# Sensor_Board.net
KiCad netlist of a schematic drawn in Altium Designer
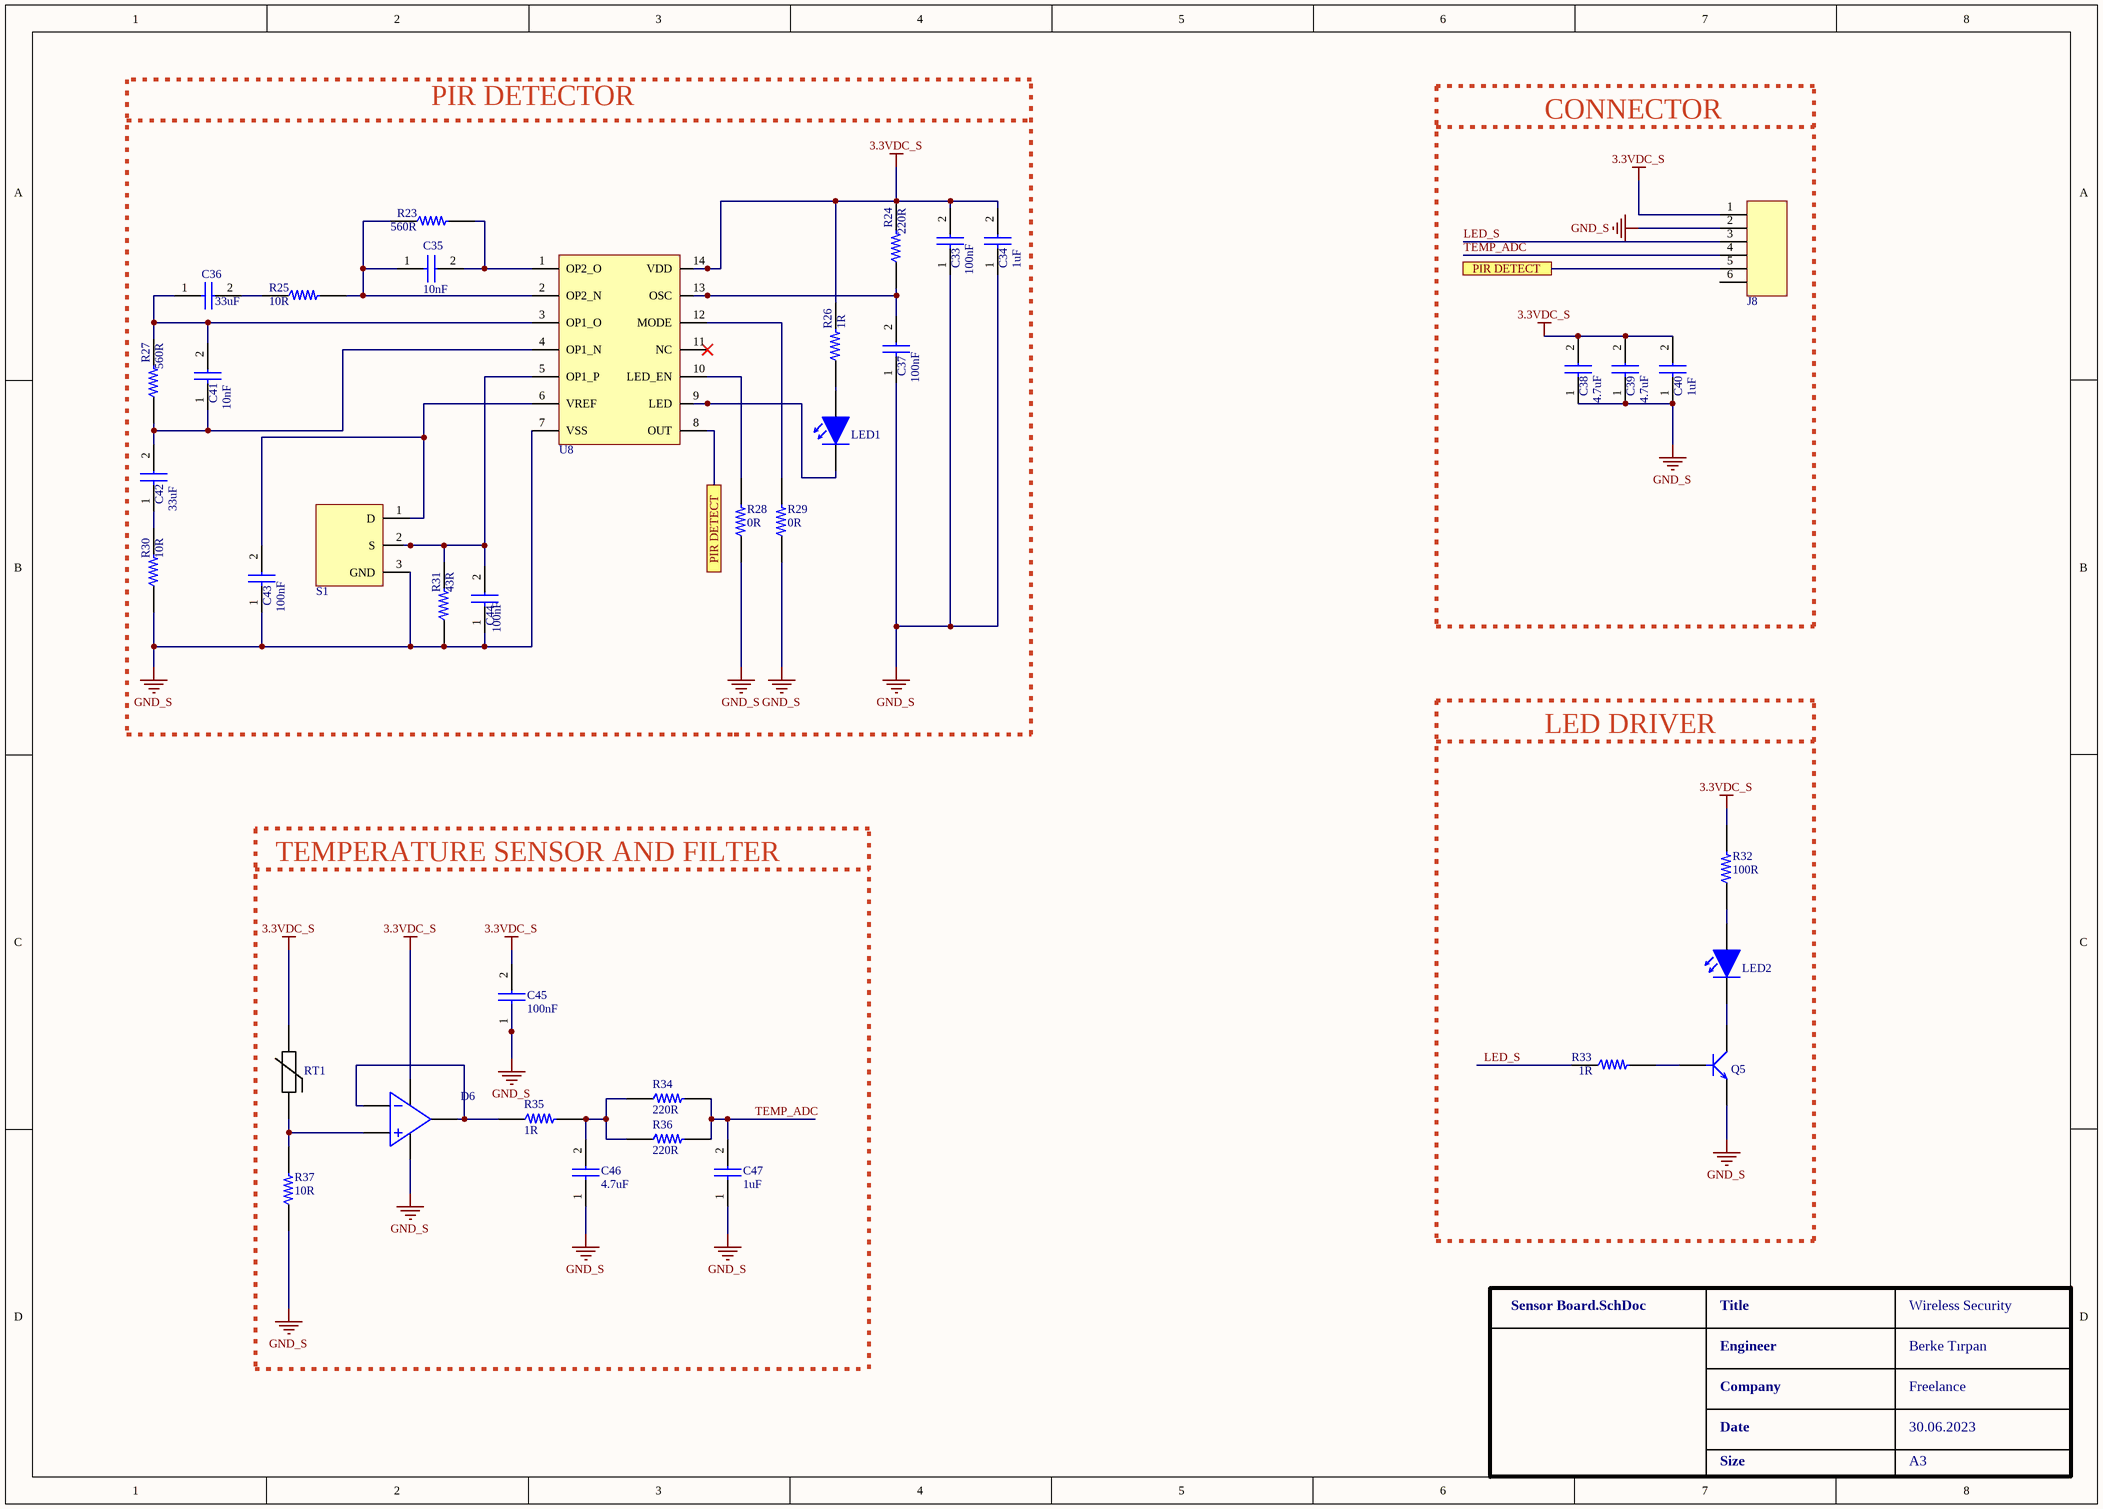
[diagram p0: Sensor Board.SchDoc]

(export (version "E")
  (design (tool "Eeschema 10.0.6"))
  (components
    (comp (ref "C33")
      (value "C0603C104K5RACTU")
      (footprint "CAP_0603")
      (description "Multilayer Ceramic Capacitors (MLCC) - SMD/SMT 50volts 0.1uF X7R 10%")
      (fields
        (field (name "MANUFACTURER") "KEMET")
        (field (name "TOLERANCE") "10%")
        (field (name "CAPACITANCE") "100nF")
      )
      (libsource (lib "Ilk Proje") (part "CAP CER 100nF 0603"))
    )
    (comp (ref "C34")
      (value "CAP CER 1uF 0805")
      (footprint "CAP_0805")
      (description "CAP CER 1UF 50V X7R %10 0805")
      (fields
        (field (name "MANUFACTURER") "Samsung")
        (field (name "MANUFACTURER PART NUMBER") "CL21B105KBFNNNE")
        (field (name "CAPACITANCE") "1uF")
      )
      (libsource (lib "Ilk Proje") (part "CAP CER 1uF 0805"))
    )
    (comp (ref "C35")
      (value "CAP CER 10nF 0603")
      (footprint "CAP_0603")
      (description "Multilayer Ceramic Capacitor, 0.01 F, 10%, X7R, 16 V, 0603 [1608 Metric] RoHS Compliant: Yes")
      (fields
        (field (name "MANUFACTURER") "Walsin Technologies")
        (field (name "MANUFACTURER PART NUMBER") "0603B103K160CT")
        (field (name "CAPACITANCE") "10nF")
      )
      (libsource (lib "Ilk Proje") (part "CAP CER 10nF 0603"))
    )
    (comp (ref "C36")
      (value "C3216X5R1E336M160AC")
      (footprint "CAP_1206")
      (description "C Series 1206 33 uF 25 V ±20 % Tolerance X5R SMT Multilayer Ceramic Capacitor")
      (fields
        (field (name "MANUFACTURER") "TDK")
        (field (name "TOLERANCE") "20%")
        (field (name "CAPACITANCE") "33uF")
      )
      (libsource (lib "Ilk Proje") (part "CAP CER 33uF 1206"))
    )
    (comp (ref "C37")
      (value "C0603C104K5RACTU")
      (footprint "CAP_0603")
      (description "Multilayer Ceramic Capacitors (MLCC) - SMD/SMT 50volts 0.1uF X7R 10%")
      (fields
        (field (name "MANUFACTURER") "KEMET")
        (field (name "TOLERANCE") "10%")
        (field (name "CAPACITANCE") "100nF")
      )
      (libsource (lib "Ilk Proje") (part "CAP CER 100nF 0603"))
    )
    (comp (ref "C38")
      (value "CAP_CER_4,7UF_0805")
      (footprint "CAP_0805")
      (description "CAP CER 4.7UF 25V %10 0805")
      (fields
        (field (name "MANUFACTURER") "Samsung")
        (field (name "MANUFACTURER PART NUMBER") "CL21A475KAQNNNE")
        (field (name "CAPACITANCE") "4.7uF")
      )
      (libsource (lib "Ilk Proje") (part "CAP_CER_4,7UF_0805"))
    )
    (comp (ref "C39")
      (value "CAP_CER_4,7UF_0805")
      (footprint "CAP_0805")
      (description "CAP CER 4.7UF 25V %10 0805")
      (fields
        (field (name "MANUFACTURER") "Samsung")
        (field (name "MANUFACTURER PART NUMBER") "CL21A475KAQNNNE")
        (field (name "CAPACITANCE") "4.7uF")
      )
      (libsource (lib "Ilk Proje") (part "CAP_CER_4,7UF_0805"))
    )
    (comp (ref "C40")
      (value "CAP CER 1uF 0805")
      (footprint "CAP_0805")
      (description "CAP CER 1UF 50V X7R %10 0805")
      (fields
        (field (name "MANUFACTURER") "Samsung")
        (field (name "MANUFACTURER PART NUMBER") "CL21B105KBFNNNE")
        (field (name "CAPACITANCE") "1uF")
      )
      (libsource (lib "Ilk Proje") (part "CAP CER 1uF 0805"))
    )
    (comp (ref "C41")
      (value "CAP CER 10nF 0603")
      (footprint "CAP_0603")
      (description "Multilayer Ceramic Capacitor, 0.01 F, 10%, X7R, 16 V, 0603 [1608 Metric] RoHS Compliant: Yes")
      (fields
        (field (name "MANUFACTURER") "Walsin Technologies")
        (field (name "MANUFACTURER PART NUMBER") "0603B103K160CT")
        (field (name "CAPACITANCE") "10nF")
      )
      (libsource (lib "Ilk Proje") (part "CAP CER 10nF 0603"))
    )
    (comp (ref "C42")
      (value "C3216X5R1E336M160AC")
      (footprint "CAP_1206")
      (description "C Series 1206 33 uF 25 V ±20 % Tolerance X5R SMT Multilayer Ceramic Capacitor")
      (fields
        (field (name "MANUFACTURER") "TDK")
        (field (name "TOLERANCE") "20%")
        (field (name "CAPACITANCE") "33uF")
      )
      (libsource (lib "Ilk Proje") (part "CAP CER 33uF 1206"))
    )
    (comp (ref "C43")
      (value "C0603C104K5RACTU")
      (footprint "CAP_0603")
      (description "Multilayer Ceramic Capacitors (MLCC) - SMD/SMT 50volts 0.1uF X7R 10%")
      (fields
        (field (name "MANUFACTURER") "KEMET")
        (field (name "TOLERANCE") "10%")
        (field (name "CAPACITANCE") "100nF")
      )
      (libsource (lib "Ilk Proje") (part "CAP CER 100nF 0603"))
    )
    (comp (ref "C44")
      (value "C0603C104K5RACTU")
      (footprint "CAP_0603")
      (description "Multilayer Ceramic Capacitors (MLCC) - SMD/SMT 50volts 0.1uF X7R 10%")
      (fields
        (field (name "MANUFACTURER") "KEMET")
        (field (name "TOLERANCE") "10%")
        (field (name "CAPACITANCE") "100nF")
      )
      (libsource (lib "Ilk Proje") (part "CAP CER 100nF 0603"))
    )
    (comp (ref "C45")
      (value "C0603C104K5RACTU")
      (footprint "CAP_0603")
      (description "Multilayer Ceramic Capacitors (MLCC) - SMD/SMT 50volts 0.1uF X7R 10%")
      (fields
        (field (name "MANUFACTURER") "KEMET")
        (field (name "TOLERANCE") "10%")
        (field (name "CAPACITANCE") "100nF")
      )
      (libsource (lib "Ilk Proje") (part "CAP CER 100nF 0603"))
    )
    (comp (ref "C46")
      (value "CAP_CER_4,7UF_0805")
      (footprint "CAP_0805")
      (description "CAP CER 4.7UF 25V %10 0805")
      (fields
        (field (name "MANUFACTURER") "Samsung")
        (field (name "MANUFACTURER PART NUMBER") "CL21A475KAQNNNE")
        (field (name "CAPACITANCE") "4.7uF")
      )
      (libsource (lib "Ilk Proje") (part "CAP_CER_4,7UF_0805"))
    )
    (comp (ref "C47")
      (value "CAP CER 1uF 0805")
      (footprint "CAP_0805")
      (description "CAP CER 1UF 50V X7R %10 0805")
      (fields
        (field (name "MANUFACTURER") "Samsung")
        (field (name "MANUFACTURER PART NUMBER") "CL21B105KBFNNNE")
        (field (name "CAPACITANCE") "1uF")
      )
      (libsource (lib "Ilk Proje") (part "CAP CER 1uF 0805"))
    )
    (comp (ref "D6")
      (value "OPA314AIDBVR")
      (footprint "SOT23-5")
      (description "IC OPAMP GP 3MHZ RRO SOT23-5")
      (fields (field (name "MANUFACTURER") "Texas Instruments"))
      (libsource (lib "Ilk Proje") (part "OPA314"))
    )
    (comp (ref "J8")
      (value "64800611622")
      (footprint "64800611622")
      (description "WR-WTB Wire-to-Board Connectors 6PIN 1.50 mm")
      (fields (field (name "MANUFACTURER") "Wurth Electronics"))
      (libsource (lib "Ilk Proje") (part "64800611622_conn_6pin"))
    )
    (comp (ref "LED1")
      (value "LTST-C171GKT")
      (footprint "LED_GREEN_0805")
      (description "Green 569nm LED Indication - Discrete 2.1V 0805 (2012 Metric)")
      (fields (field (name "MANUFACTURER") "Vishay Lite-On"))
      (libsource (lib "Ilk Proje") (part "LED GREEN 0805"))
    )
    (comp (ref "LED2")
      (value "LH R974-LP1")
      (footprint "LED_RED_0805")
      (description "LED Uni-Color Hyper Red 660nm 2-Pin Chip 0805(2012Metric) T/R")
      (fields (field (name "MFR") "ams-OSRAN USA INC."))
      (libsource (lib "Ilk Proje") (part "LED RED 0805"))
    )
    (comp (ref "Q5")
      (value "MMBT3904-7-F")
      (footprint "SOT23-F")
      (description "NPN Ic=200mA Vceo=40V hfe=100~300 fT=310MHz P=300mW SOT-23")
      (fields (field (name "MANUFACTURER") "Diodes Zetex"))
      (libsource (lib "Ilk Proje") (part "MMBT3904-7-F"))
    )
    (comp (ref "R23")
      (value "RC0603JR-07560KL")
      (footprint "RES_0603")
      (description "Res Thick Film 0603 560K Ohm 5% 0.1W(1/10W) ±100ppm/C Molded SMD Paper T/R")
      (fields
        (field (name "MANUFACTURER") "Yageo")
        (field (name "TOLERANCE") "5%")
        (field (name "RESISTANCE") "560R")
      )
      (libsource (lib "Ilk Proje") (part "RES 560K OHM 0603"))
    )
    (comp (ref "R24")
      (value "RC0603JR-07220KL")
      (footprint "RES_0603")
      (description "Res Thick Film 0603 220K Ohm 5% 0.1W(1/10W) ±100ppm/C Pad SMD T/R")
      (fields
        (field (name "MANUFACTURER") "Yageo")
        (field (name "TOLERANCE") "5%")
        (field (name "RESISTANCE") "220R")
      )
      (libsource (lib "Ilk Proje") (part "RES 220K OHM 0603"))
    )
    (comp (ref "R25")
      (value "RC0603FR-0710KL")
      (footprint "RES_0603")
      (description "RES SMD 10K OHM 1% 1/10W 0603")
      (fields
        (field (name "MANUFACTURER") "Yageo")
        (field (name "TOLERANCE") "1%")
        (field (name "RESISTANCE") "10R")
      )
      (libsource (lib "Ilk Proje") (part "RES 10K OHM 0603"))
    )
    (comp (ref "R26")
      (value "RT0603BRD071KL")
      (footprint "RES_0603")
      (description "High Precision-High Stability Chip Resistor Thin Film 0603 1kOhm 0.1% Paper T/R")
      (fields (field (name "MANUFACTURER") "Yageo") (field (name "RESISTANCE") "1R"))
      (libsource (lib "Ilk Proje") (part "RES 1K OHM 0603"))
    )
    (comp (ref "R27")
      (value "RC0603JR-07560KL")
      (footprint "RES_0603")
      (description "Res Thick Film 0603 560K Ohm 5% 0.1W(1/10W) ±100ppm/C Molded SMD Paper T/R")
      (fields
        (field (name "MANUFACTURER") "Yageo")
        (field (name "TOLERANCE") "5%")
        (field (name "RESISTANCE") "560R")
      )
      (libsource (lib "Ilk Proje") (part "RES 560K OHM 0603"))
    )
    (comp (ref "R28")
      (value "RC0603JR-070RL")
      (footprint "RES_0603")
      (description "RES SMD 0 OHM JUMPER 1/10W 0603")
      (fields
        (field (name "MANUFACTURER") "Yageo")
        (field (name "TOLERANCE") "1%")
        (field (name "RESISTANCE") "0R")
      )
      (libsource (lib "Ilk Proje") (part "RES 0 OHM 0603"))
    )
    (comp (ref "R29")
      (value "RC0603JR-070RL")
      (footprint "RES_0603")
      (description "RES SMD 0 OHM JUMPER 1/10W 0603")
      (fields
        (field (name "MANUFACTURER") "Yageo")
        (field (name "TOLERANCE") "1%")
        (field (name "RESISTANCE") "0R")
      )
      (libsource (lib "Ilk Proje") (part "RES 0 OHM 0603"))
    )
    (comp (ref "R30")
      (value "RC0603FR-0710KL")
      (footprint "RES_0603")
      (description "RES SMD 10K OHM 1% 1/10W 0603")
      (fields
        (field (name "MANUFACTURER") "Yageo")
        (field (name "TOLERANCE") "1%")
        (field (name "RESISTANCE") "10R")
      )
      (libsource (lib "Ilk Proje") (part "RES 10K OHM 0603"))
    )
    (comp (ref "R31")
      (value "RC0603JR-0743KL")
      (footprint "RES_0603")
      (description "Res Thick Film 0603 43K Ohm 5% 0.1W(1/10W) ±100ppm/°C Pad SMD T/R")
      (fields
        (field (name "MANUFACTURER") "Yageo")
        (field (name "TOLERANCE") "5%")
        (field (name "RESISTANCE") "43R")
      )
      (libsource (lib "Ilk Proje") (part "RES 43K OHM 0603"))
    )
    (comp (ref "R32")
      (value "RC0603FR-07100KL")
      (footprint "RES_0603")
      (description "RES SMD 100K OHM 1% 1/10W 0603")
      (fields
        (field (name "MANUFACTURER") "Yageo")
        (field (name "TOLERANCE") "1%")
        (field (name "RESISTANCE") "100R")
      )
      (libsource (lib "Ilk Proje") (part "RES 100K OHM 0603"))
    )
    (comp (ref "R33")
      (value "RT0603BRD071KL")
      (footprint "RES_0603")
      (description "High Precision-High Stability Chip Resistor Thin Film 0603 1kOhm 0.1% Paper T/R")
      (fields (field (name "MANUFACTURER") "Yageo") (field (name "RESISTANCE") "1R"))
      (libsource (lib "Ilk Proje") (part "RES 1K OHM 0603"))
    )
    (comp (ref "R34")
      (value "RC0603JR-07220KL")
      (footprint "RES_0603")
      (description "Res Thick Film 0603 220K Ohm 5% 0.1W(1/10W) ±100ppm/C Pad SMD T/R")
      (fields
        (field (name "MANUFACTURER") "Yageo")
        (field (name "TOLERANCE") "5%")
        (field (name "RESISTANCE") "220R")
      )
      (libsource (lib "Ilk Proje") (part "RES 220K OHM 0603"))
    )
    (comp (ref "R35")
      (value "RT0603BRD071KL")
      (footprint "RES_0603")
      (description "High Precision-High Stability Chip Resistor Thin Film 0603 1kOhm 0.1% Paper T/R")
      (fields (field (name "MANUFACTURER") "Yageo") (field (name "RESISTANCE") "1R"))
      (libsource (lib "Ilk Proje") (part "RES 1K OHM 0603"))
    )
    (comp (ref "R36")
      (value "RC0603JR-07220KL")
      (footprint "RES_0603")
      (description "Res Thick Film 0603 220K Ohm 5% 0.1W(1/10W) ±100ppm/C Pad SMD T/R")
      (fields
        (field (name "MANUFACTURER") "Yageo")
        (field (name "TOLERANCE") "5%")
        (field (name "RESISTANCE") "220R")
      )
      (libsource (lib "Ilk Proje") (part "RES 220K OHM 0603"))
    )
    (comp (ref "R37")
      (value "RC0603FR-0710KL")
      (footprint "RES_0603")
      (description "RES SMD 10K OHM 1% 1/10W 0603")
      (fields
        (field (name "MANUFACTURER") "Yageo")
        (field (name "TOLERANCE") "1%")
        (field (name "RESISTANCE") "10R")
      )
      (libsource (lib "Ilk Proje") (part "RES 10K OHM 0603"))
    )
    (comp (ref "RT1")
      (value "TFPT1206L1002FM")
      (footprint "RES_1206")
      (description "Thermistor PTC 10K Ohm 1% 1206")
      (fields (field (name "MANUFACTURER") "Vishay Dale") (field (name "TOLERANCE") "1%"))
      (libsource (lib "Ilk Proje") (part "TFPT1206L1002FM"))
    )
    (comp (ref "S1")
      (value "LHI 878/3902")
      (footprint "LHI 878")
      (description "SENSOR PYRO DETECTOR DUAL MOTION")
      (libsource (lib "Ilk Proje") (part "LHI 878/3902"))
    )
    (comp (ref "U8")
      (value "NCS36000DRG")
      (footprint "SOIC14")
      (description "PIR CONTROLLER NCS36000 Series Single 5.75V Passive Infrared Detector Controller (PIR) -SOIC-14")
      (fields (field (name "MANUFACTURER") "ON Semiconductor"))
      (libsource (lib "Ilk Proje") (part "NCS36000"))
    )
  )
  (nets
    (net (code "1") (name "/LED_S") (class "Default")
      (node (ref "J8") (pin "3") (pintype "power_in"))
      (node (ref "R33") (pin "1") (pinfunction "1_1") (pintype "passive"))
    )
    (net (code "2") (name "/PIR DETECT") (class "Default")
      (node (ref "J8") (pin "5") (pintype "power_in"))
      (node (ref "U8") (pin "8") (pinfunction "OUT_8") (pintype "passive"))
    )
    (net (code "3") (name "/TEMP_ADC") (class "Default")
      (node (ref "C47") (pin "2") (pinfunction "2_2") (pintype "passive"))
      (node (ref "J8") (pin "4") (pintype "power_in"))
      (node (ref "R34") (pin "2") (pinfunction "2_2") (pintype "passive"))
      (node (ref "R36") (pin "2") (pinfunction "2_2") (pintype "passive"))
    )
    (net (code "4") (name "3.3VDC_S") (class "Default")
      (node (ref "C33") (pin "2") (pinfunction "2_2") (pintype "passive"))
      (node (ref "C34") (pin "2") (pinfunction "2_2") (pintype "passive"))
      (node (ref "C38") (pin "2") (pinfunction "2_2") (pintype "passive"))
      (node (ref "C39") (pin "2") (pinfunction "2_2") (pintype "passive"))
      (node (ref "C40") (pin "2") (pinfunction "2_2") (pintype "passive"))
      (node (ref "C45") (pin "2") (pinfunction "2_2") (pintype "passive"))
      (node (ref "D6") (pin "5") (pinfunction "5_5") (pintype "passive"))
      (node (ref "J8") (pin "1") (pintype "power_in"))
      (node (ref "R24") (pin "2") (pinfunction "2_2") (pintype "passive"))
      (node (ref "R26") (pin "2") (pinfunction "2_2") (pintype "passive"))
      (node (ref "R32") (pin "2") (pinfunction "2_2") (pintype "passive"))
      (node (ref "RT1") (pin "2") (pinfunction "2_2") (pintype "passive"))
      (node (ref "U8") (pin "14") (pinfunction "VDD_14") (pintype "passive"))
    )
    (net (code "5") (name "GND_S") (class "Default")
      (node (ref "C33") (pin "1") (pinfunction "1_1") (pintype "passive"))
      (node (ref "C34") (pin "1") (pinfunction "1_1") (pintype "passive"))
      (node (ref "C37") (pin "1") (pinfunction "1_1") (pintype "passive"))
      (node (ref "C38") (pin "1") (pinfunction "1_1") (pintype "passive"))
      (node (ref "C39") (pin "1") (pinfunction "1_1") (pintype "passive"))
      (node (ref "C40") (pin "1") (pinfunction "1_1") (pintype "passive"))
      (node (ref "C43") (pin "1") (pinfunction "1_1") (pintype "passive"))
      (node (ref "C44") (pin "1") (pinfunction "1_1") (pintype "passive"))
      (node (ref "C45") (pin "1") (pinfunction "1_1") (pintype "passive"))
      (node (ref "C46") (pin "1") (pinfunction "1_1") (pintype "passive"))
      (node (ref "C47") (pin "1") (pinfunction "1_1") (pintype "passive"))
      (node (ref "D6") (pin "2") (pinfunction "2_2") (pintype "passive"))
      (node (ref "J8") (pin "2") (pintype "power_in"))
      (node (ref "Q5") (pin "2") (pinfunction "E_2") (pintype "power_in"))
      (node (ref "R28") (pin "1") (pinfunction "1_1") (pintype "passive"))
      (node (ref "R29") (pin "1") (pinfunction "1_1") (pintype "passive"))
      (node (ref "R30") (pin "1") (pinfunction "1_1") (pintype "passive"))
      (node (ref "R31") (pin "1") (pinfunction "1_1") (pintype "passive"))
      (node (ref "R37") (pin "1") (pinfunction "1_1") (pintype "passive"))
      (node (ref "S1") (pin "3") (pinfunction "GND_3") (pintype "passive"))
      (node (ref "U8") (pin "7") (pinfunction "VSS_7") (pintype "passive"))
    )
    (net (code "6") (name "Net-(C36-Pad2)") (class "Default")
      (node (ref "C36") (pin "2") (pinfunction "2_2") (pintype "passive"))
      (node (ref "R25") (pin "1") (pinfunction "1_1") (pintype "passive"))
    )
    (net (code "7") (name "Net-(C42-Pad1)") (class "Default")
      (node (ref "C42") (pin "1") (pinfunction "1_1") (pintype "passive"))
      (node (ref "R30") (pin "2") (pinfunction "2_2") (pintype "passive"))
    )
    (net (code "8") (name "Net-(C46-Pad2)") (class "Default")
      (node (ref "C46") (pin "2") (pinfunction "2_2") (pintype "passive"))
      (node (ref "R34") (pin "1") (pinfunction "1_1") (pintype "passive"))
      (node (ref "R35") (pin "2") (pinfunction "2_2") (pintype "passive"))
      (node (ref "R36") (pin "1") (pinfunction "1_1") (pintype "passive"))
    )
    (net (code "9") (name "Net-(D6-Pad1)") (class "Default")
      (node (ref "D6") (pin "1") (pinfunction "1_1") (pintype "passive"))
      (node (ref "D6") (pin "4") (pinfunction "4_4") (pintype "passive"))
      (node (ref "R35") (pin "1") (pinfunction "1_1") (pintype "passive"))
    )
    (net (code "10") (name "Net-(D6-Pad3)") (class "Default")
      (node (ref "D6") (pin "3") (pinfunction "3_3") (pintype "passive"))
      (node (ref "R37") (pin "2") (pinfunction "2_2") (pintype "passive"))
      (node (ref "RT1") (pin "1") (pinfunction "1_1") (pintype "passive"))
    )
    (net (code "11") (name "Net-(LED1-Pad2)") (class "Default")
      (node (ref "LED1") (pin "2") (pinfunction "2_2") (pintype "power_in"))
      (node (ref "R26") (pin "1") (pinfunction "1_1") (pintype "passive"))
    )
    (net (code "12") (name "Net-(LED2-Pad2)") (class "Default")
      (node (ref "LED2") (pin "2") (pinfunction "2_2") (pintype "power_in"))
      (node (ref "R32") (pin "1") (pinfunction "1_1") (pintype "passive"))
    )
    (net (code "13") (name "Net-(Q5-B)") (class "Default")
      (node (ref "Q5") (pin "1") (pinfunction "B_1") (pintype "power_in"))
      (node (ref "R33") (pin "2") (pinfunction "2_2") (pintype "passive"))
    )
    (net (code "14") (name "Net-(Q5-C)") (class "Default")
      (node (ref "LED2") (pin "1") (pinfunction "1_1") (pintype "power_in"))
      (node (ref "Q5") (pin "3") (pinfunction "C_3") (pintype "power_in"))
    )
    (net (code "15") (name "Net-(S1-D)") (class "Default")
      (node (ref "C43") (pin "2") (pinfunction "2_2") (pintype "passive"))
      (node (ref "S1") (pin "1") (pinfunction "D_1") (pintype "passive"))
      (node (ref "U8") (pin "6") (pinfunction "VREF_6") (pintype "passive"))
    )
    (net (code "16") (name "Net-(S1-S)") (class "Default")
      (node (ref "C44") (pin "2") (pinfunction "2_2") (pintype "passive"))
      (node (ref "R31") (pin "2") (pinfunction "2_2") (pintype "passive"))
      (node (ref "S1") (pin "2") (pinfunction "S_2") (pintype "passive"))
      (node (ref "U8") (pin "5") (pinfunction "OP1_P_5") (pintype "passive"))
    )
    (net (code "17") (name "Net-(U8-LED)") (class "Default")
      (node (ref "LED1") (pin "1") (pinfunction "1_1") (pintype "power_in"))
      (node (ref "U8") (pin "9") (pinfunction "LED_9") (pintype "passive"))
    )
    (net (code "18") (name "Net-(U8-LED_EN)") (class "Default")
      (node (ref "R28") (pin "2") (pinfunction "2_2") (pintype "passive"))
      (node (ref "U8") (pin "10") (pinfunction "LED_EN_10") (pintype "passive"))
    )
    (net (code "19") (name "Net-(U8-MODE)") (class "Default")
      (node (ref "R29") (pin "2") (pinfunction "2_2") (pintype "passive"))
      (node (ref "U8") (pin "12") (pinfunction "MODE_12") (pintype "passive"))
    )
    (net (code "20") (name "Net-(U8-OP1_N)") (class "Default")
      (node (ref "C41") (pin "1") (pinfunction "1_1") (pintype "passive"))
      (node (ref "C42") (pin "2") (pinfunction "2_2") (pintype "passive"))
      (node (ref "R27") (pin "1") (pinfunction "1_1") (pintype "passive"))
      (node (ref "U8") (pin "4") (pinfunction "OP1_N_4") (pintype "passive"))
    )
    (net (code "21") (name "Net-(U8-OP1_O)") (class "Default")
      (node (ref "C36") (pin "1") (pinfunction "1_1") (pintype "passive"))
      (node (ref "C41") (pin "2") (pinfunction "2_2") (pintype "passive"))
      (node (ref "R27") (pin "2") (pinfunction "2_2") (pintype "passive"))
      (node (ref "U8") (pin "3") (pinfunction "OP1_O_3") (pintype "passive"))
    )
    (net (code "22") (name "Net-(U8-OP2_N)") (class "Default")
      (node (ref "C35") (pin "1") (pinfunction "1_1") (pintype "passive"))
      (node (ref "R23") (pin "1") (pinfunction "1_1") (pintype "passive"))
      (node (ref "R25") (pin "2") (pinfunction "2_2") (pintype "passive"))
      (node (ref "U8") (pin "2") (pinfunction "OP2_N_2") (pintype "passive"))
    )
    (net (code "23") (name "Net-(U8-OP2_O)") (class "Default")
      (node (ref "C35") (pin "2") (pinfunction "2_2") (pintype "passive"))
      (node (ref "R23") (pin "2") (pinfunction "2_2") (pintype "passive"))
      (node (ref "U8") (pin "1") (pinfunction "OP2_O_1") (pintype "passive"))
    )
    (net (code "24") (name "Net-(U8-OSC)") (class "Default")
      (node (ref "C37") (pin "2") (pinfunction "2_2") (pintype "passive"))
      (node (ref "R24") (pin "1") (pinfunction "1_1") (pintype "passive"))
      (node (ref "U8") (pin "13") (pinfunction "OSC_13") (pintype "passive"))
    )
    (net (code "25") (name "unconnected-(J8-Pad6)") (class "Default")
      (node (ref "J8") (pin "6") (pintype "power_in"))
    )
    (net (code "26") (name "unconnected-(U8-NC-Pad11)") (class "Default")
      (node (ref "U8") (pin "11") (pinfunction "NC_11") (pintype "passive+no_connect"))
    )
  )
)
